# main.net
KiCad netlist of a schematic drawn in EAGLE
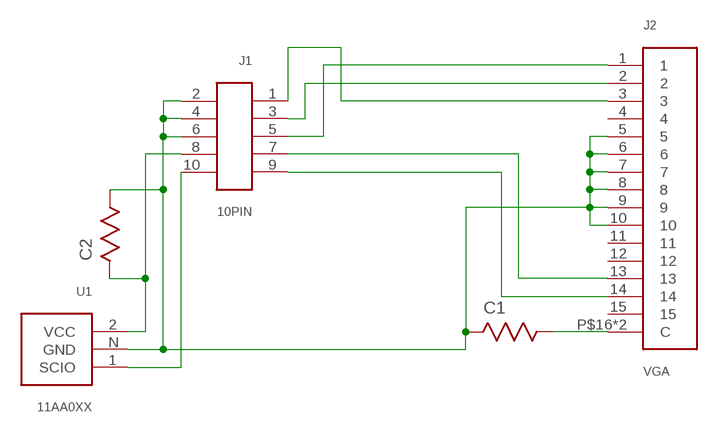
[diagram p0: schematic, sheet 1]

(export (version "E")
  (design (tool "Eeschema 10.0.6"))
  (components
    (comp (ref "C1")
      (value "RESISTOR0603")
      (footprint "eagle-import:0603")
      (libsource (lib "eagle-import") (part "RESISTOR0603"))
    )
    (comp (ref "C2")
      (value "RESISTOR0603")
      (footprint "eagle-import:0603")
      (libsource (lib "eagle-import") (part "RESISTOR0603"))
    )
    (comp (ref "J1")
      (value "10PIN")
      (footprint "eagle-import:10PIN")
      (libsource (lib "eagle-import") (part "10PIN"))
    )
    (comp (ref "J2")
      (value "VGA")
      (footprint "eagle-import:VGA")
      (libsource (lib "eagle-import") (part "VGA"))
    )
    (comp (ref "U1")
      (value "11AA0XX")
      (footprint "eagle-import:SOT-23")
      (libsource (lib "eagle-import") (part "11AA0XX"))
    )
  )
  (nets
    (net (code "1") (name "Net-(C1-PadP$2)") (class "Default")
      (node (ref "C1") (pin "P$2") (pinfunction "P$2_P$2") (pintype "bidirectional"))
      (node (ref "J2") (pin "P$16") (pinfunction "C_P$16") (pintype "bidirectional"))
      (node (ref "J2") (pin "P$17") (pinfunction "C_P$17") (pintype "bidirectional"))
    )
    (net (code "2") (name "Net-(J1-Pad1)") (class "Default")
      (node (ref "J1") (pin "1") (pinfunction "1_1") (pintype "bidirectional"))
      (node (ref "J2") (pin "3") (pinfunction "3_3") (pintype "bidirectional"))
    )
    (net (code "3") (name "Net-(J1-Pad3)") (class "Default")
      (node (ref "J1") (pin "3") (pinfunction "3_3") (pintype "bidirectional"))
      (node (ref "J2") (pin "2") (pinfunction "2_2") (pintype "bidirectional"))
    )
    (net (code "4") (name "Net-(J1-Pad5)") (class "Default")
      (node (ref "J1") (pin "5") (pinfunction "5_5") (pintype "bidirectional"))
      (node (ref "J2") (pin "1") (pinfunction "1_1") (pintype "bidirectional"))
    )
    (net (code "5") (name "Net-(J1-Pad7)") (class "Default")
      (node (ref "J1") (pin "7") (pinfunction "7_7") (pintype "bidirectional"))
      (node (ref "J2") (pin "13") (pinfunction "13_13") (pintype "bidirectional"))
    )
    (net (code "6") (name "Net-(J1-Pad9)") (class "Default")
      (node (ref "J1") (pin "9") (pinfunction "9_9") (pintype "bidirectional"))
      (node (ref "J2") (pin "14") (pinfunction "14_14") (pintype "bidirectional"))
    )
    (net (code "7") (name "Net-(U1-GND)") (class "Default")
      (node (ref "C1") (pin "P$1") (pinfunction "P$1_P$1") (pintype "bidirectional"))
      (node (ref "C2") (pin "P$2") (pinfunction "P$2_P$2") (pintype "bidirectional"))
      (node (ref "J1") (pin "2") (pinfunction "2_2") (pintype "bidirectional"))
      (node (ref "J1") (pin "4") (pinfunction "4_4") (pintype "bidirectional"))
      (node (ref "J1") (pin "6") (pinfunction "6_6") (pintype "bidirectional"))
      (node (ref "J2") (pin "10") (pinfunction "10_10") (pintype "bidirectional"))
      (node (ref "J2") (pin "5") (pinfunction "5_5") (pintype "bidirectional"))
      (node (ref "J2") (pin "6") (pinfunction "6_6") (pintype "bidirectional"))
      (node (ref "J2") (pin "7") (pinfunction "7_7") (pintype "bidirectional"))
      (node (ref "J2") (pin "8") (pinfunction "8_8") (pintype "bidirectional"))
      (node (ref "J2") (pin "9") (pinfunction "9_9") (pintype "bidirectional"))
      (node (ref "U1") (pin "N") (pinfunction "GND_N") (pintype "bidirectional"))
    )
    (net (code "8") (name "Net-(U1-SCIO)") (class "Default")
      (node (ref "J1") (pin "10") (pinfunction "10_10") (pintype "bidirectional"))
      (node (ref "U1") (pin "1") (pinfunction "SCIO_1") (pintype "bidirectional"))
    )
    (net (code "9") (name "Net-(U1-VCC)") (class "Default")
      (node (ref "C2") (pin "P$1") (pinfunction "P$1_P$1") (pintype "bidirectional"))
      (node (ref "J1") (pin "8") (pinfunction "8_8") (pintype "bidirectional"))
      (node (ref "U1") (pin "2") (pinfunction "VCC_2") (pintype "bidirectional"))
    )
    (net (code "10") (name "unconnected-(J2-Pad4)") (class "Default")
      (node (ref "J2") (pin "4") (pinfunction "4_4") (pintype "bidirectional"))
    )
    (net (code "11") (name "unconnected-(J2-Pad11)") (class "Default")
      (node (ref "J2") (pin "11") (pinfunction "11_11") (pintype "bidirectional"))
    )
    (net (code "12") (name "unconnected-(J2-Pad12)") (class "Default")
      (node (ref "J2") (pin "12") (pinfunction "12_12") (pintype "bidirectional"))
    )
    (net (code "13") (name "unconnected-(J2-Pad15)") (class "Default")
      (node (ref "J2") (pin "15") (pinfunction "15_15") (pintype "bidirectional"))
    )
  )
)
